# LDO_regulator.net
KiCad netlist of a schematic drawn in Altium Designer
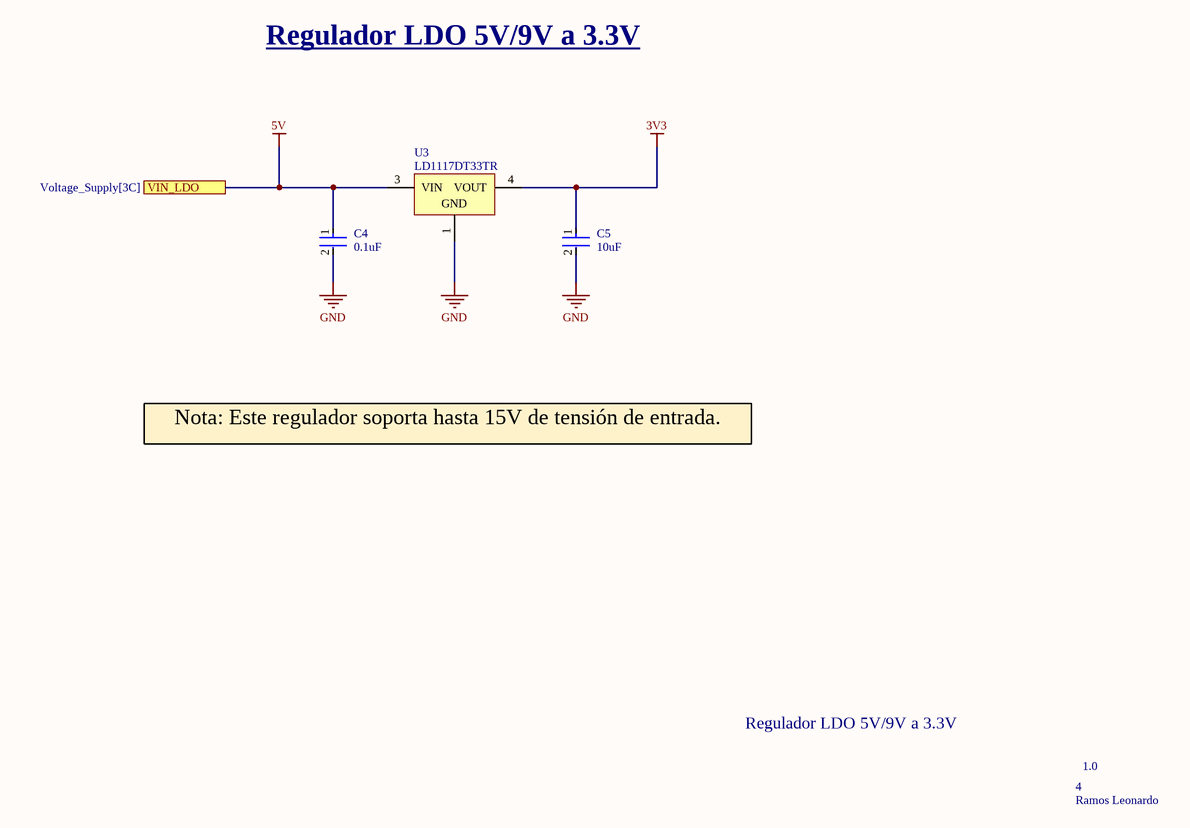
[diagram p0: LDO_regulator.SchDoc]

(export (version "E")
  (design (tool "Eeschema 10.0.6"))
  (components
    (comp (ref "C4")
      (value "0.1u")
      (footprint "FP-GRM21B-0_1-IPC_B")
      (description "Chip Multilayer Ceramic Capacitors for General Purpose, 0805, 0.10uF, U2J, -750ppm/°C, 5%, 10V")
      (fields (field (name "CAPACITANCE") "0.1uF") (field (name "TOLERANCE") "5%"))
      (libsource (lib "Altium Content Vault") (part "b4654b650e69147ec39a6b967a45e02"))
    )
    (comp (ref "C5")
      (value "10u")
      (footprint "FP-C0805C106J8RACAUTO-MFG")
      (description "CAP CER 10UF 10V X7R 0805")
      (fields (field (name "CAPACITANCE") "10uF") (field (name "TOLERANCE") "5%"))
      (libsource (lib "Altium Content Vault") (part "02cd4be3c70576c341d710602a673aa"))
    )
    (comp (ref "U3")
      (value "LD1117DT33TR")
      (footprint "TO-252_N")
      (description "Fixed Low Drop Positive Voltage Regulator, 3.3V, 3-Pin DPAK, Tape and Reel")
      (libsource (lib "Componentes_custom") (part "LD1117DT33TR"))
    )
  )
  (nets
    (net (code "1") (name "3V3") (class "Default")
      (node (ref "C5") (pin "1") (pinfunction "1_1") (pintype "passive"))
      (node (ref "U3") (pin "4") (pinfunction "VOUT_4") (pintype "power_in"))
    )
    (net (code "2") (name "5V") (class "Default")
      (node (ref "C4") (pin "1") (pinfunction "1_1") (pintype "passive"))
      (node (ref "U3") (pin "3") (pinfunction "VIN_3") (pintype "power_in"))
    )
    (net (code "3") (name "GND") (class "Default")
      (node (ref "C4") (pin "2") (pinfunction "2_2") (pintype "passive"))
      (node (ref "C5") (pin "2") (pinfunction "2_2") (pintype "passive"))
      (node (ref "U3") (pin "1") (pinfunction "GND_1") (pintype "power_in"))
    )
  )
)
